# pc_max86150_breakout_qwiic2part_part2.net
KiCad netlist of a schematic drawn in EAGLE
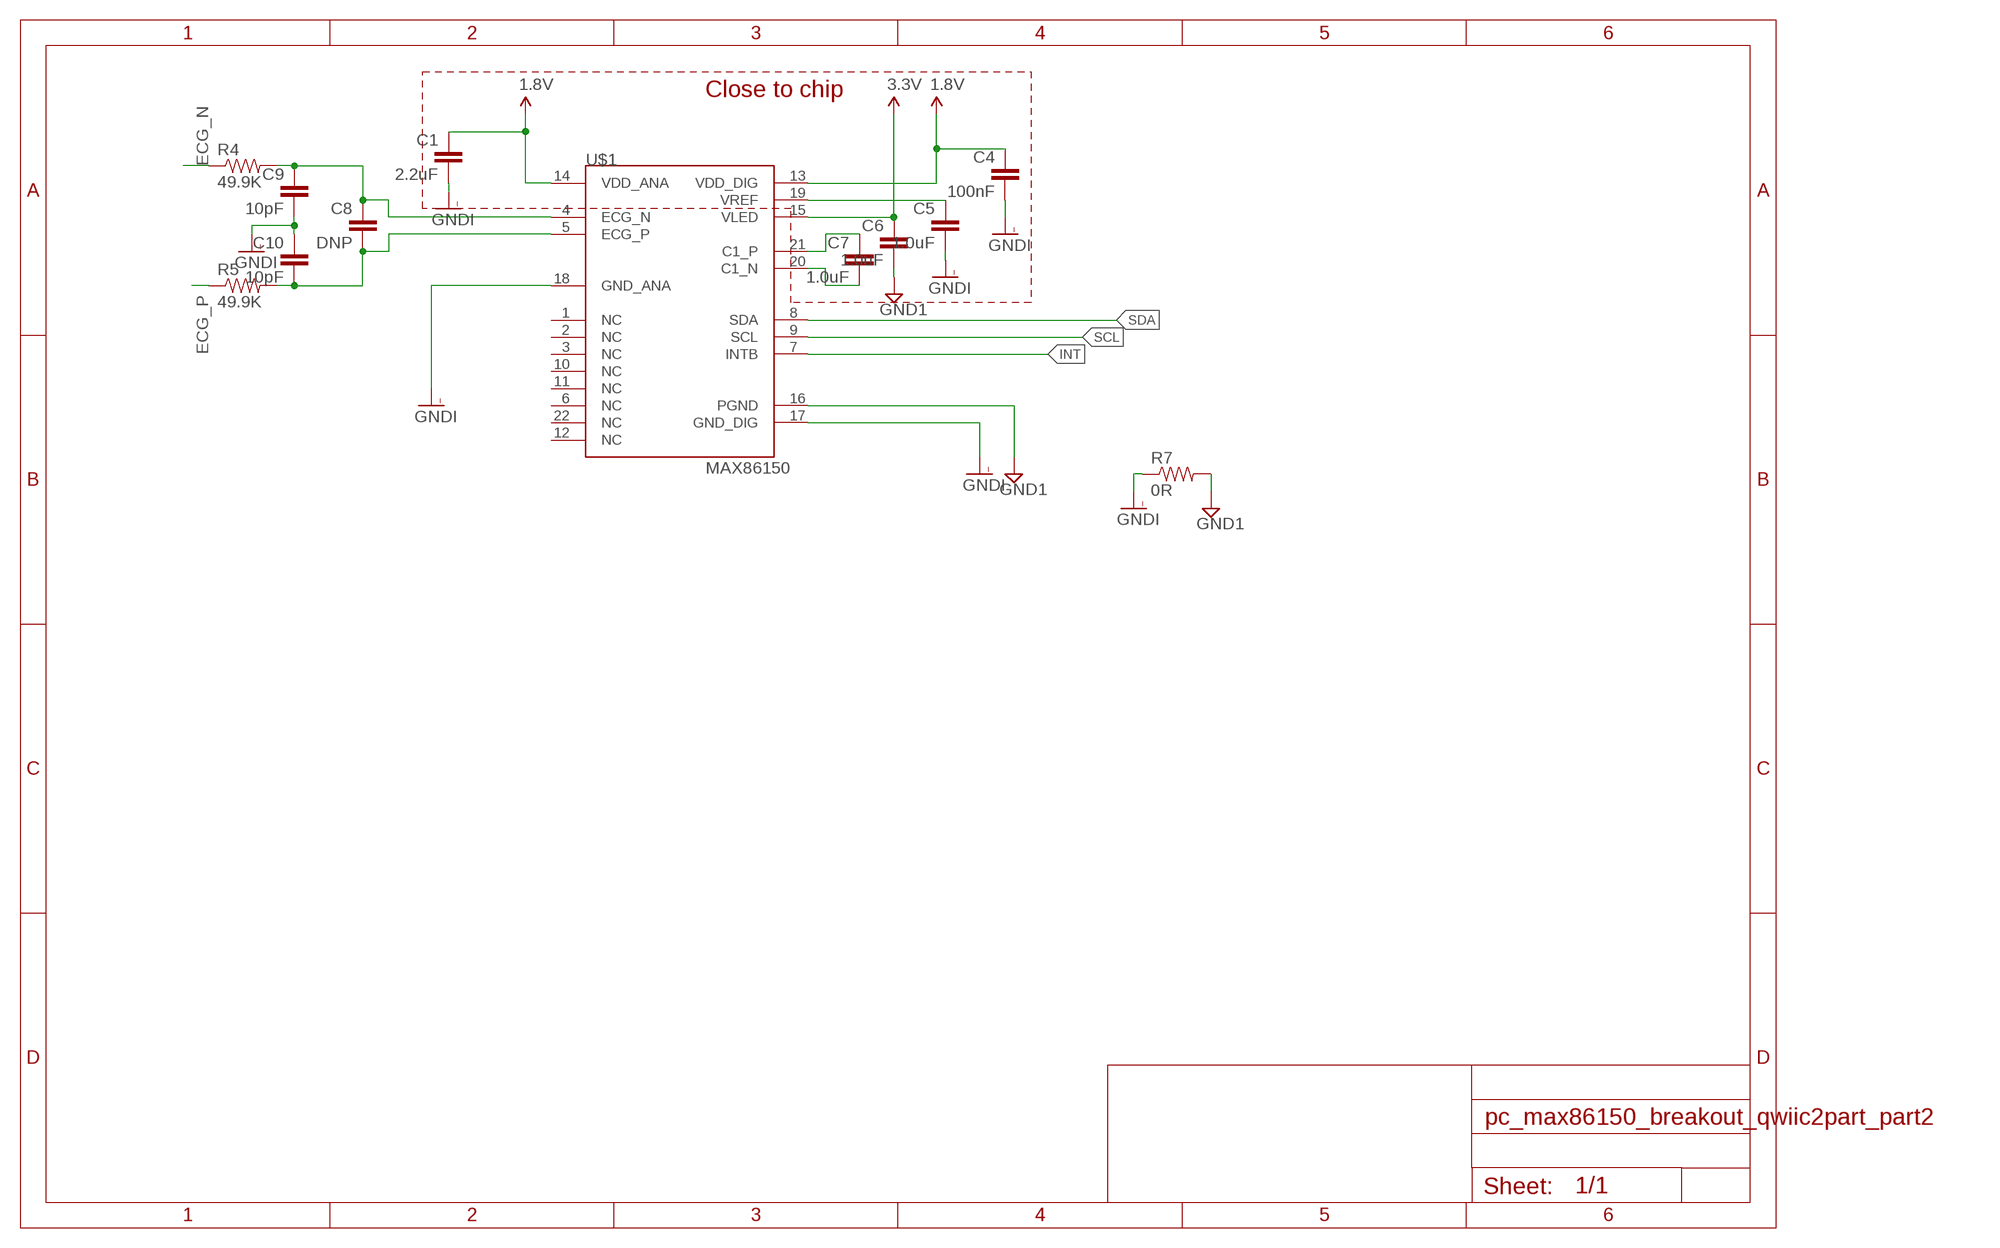
[diagram p0: schematic, sheet 1]

(export (version "E")
  (design (tool "Eeschema 10.0.6"))
  (components
    (comp (ref "C1")
      (value "2.2uF")
      (footprint "eagle-import:0402")
      (libsource (lib "eagle-import") (part "1.0UF-0402-16V-10%"))
    )
    (comp (ref "C4")
      (value "100nF")
      (footprint "eagle-import:0402")
      (libsource (lib "eagle-import") (part "1.0UF-0402-16V-10%"))
    )
    (comp (ref "C5")
      (value "1.0uF")
      (footprint "eagle-import:0402")
      (libsource (lib "eagle-import") (part "1.0UF-0402-16V-10%"))
    )
    (comp (ref "C6")
      (value "1.0uF")
      (footprint "eagle-import:0402")
      (libsource (lib "eagle-import") (part "1.0UF-0402-16V-10%"))
    )
    (comp (ref "C7")
      (value "1.0uF")
      (footprint "eagle-import:0402")
      (libsource (lib "eagle-import") (part "1.0UF-0402-16V-10%"))
    )
    (comp (ref "C8")
      (value "DNP")
      (footprint "eagle-import:0402")
      (libsource (lib "eagle-import") (part "1.0UF-0402-16V-10%"))
    )
    (comp (ref "C9")
      (value "10pF")
      (footprint "eagle-import:0402")
      (libsource (lib "eagle-import") (part "1.0UF-0402-16V-10%"))
    )
    (comp (ref "C10")
      (value "10pF")
      (footprint "eagle-import:0402")
      (libsource (lib "eagle-import") (part "1.0UF-0402-16V-10%"))
    )
    (comp (ref "R4")
      (value "49.9K")
      (footprint "eagle-import:0402-RES")
      (libsource (lib "eagle-import") (part "RESISTOR0402-RES"))
    )
    (comp (ref "R5")
      (value "49.9K")
      (footprint "eagle-import:0402-RES")
      (libsource (lib "eagle-import") (part "RESISTOR0402-RES"))
    )
    (comp (ref "R7")
      (value "0R")
      (footprint "eagle-import:0402-RES")
      (libsource (lib "eagle-import") (part "RESISTOR0402-RES"))
    )
    (comp (ref "U$1")
      (value "MAX86150")
      (footprint "eagle-import:MAX86150")
      (libsource (lib "eagle-import") (part "MAX86150"))
    )
  )
  (nets
    (net (code "1") (name "/ECG_N") (class "Default")
      (node (ref "R4") (pin "1") (pinfunction "1_1") (pintype "passive"))
    )
    (net (code "2") (name "/ECG_P") (class "Default")
      (node (ref "R5") (pin "1") (pinfunction "1_1") (pintype "passive"))
    )
    (net (code "3") (name "1.8V") (class "Default")
      (node (ref "C1") (pin "1") (pinfunction "1_1") (pintype "passive"))
      (node (ref "C4") (pin "1") (pinfunction "1_1") (pintype "passive"))
      (node (ref "U$1") (pin "13") (pinfunction "VDD_DIG_13") (pintype "bidirectional"))
      (node (ref "U$1") (pin "14") (pinfunction "VDD_ANA_14") (pintype "bidirectional"))
    )
    (net (code "4") (name "3.3V") (class "Default")
      (node (ref "C6") (pin "1") (pinfunction "1_1") (pintype "passive"))
      (node (ref "U$1") (pin "15") (pinfunction "VLED_15") (pintype "bidirectional"))
    )
    (net (code "5") (name "GND1") (class "Default")
      (node (ref "C6") (pin "2") (pinfunction "2_2") (pintype "passive"))
      (node (ref "R7") (pin "2") (pinfunction "2_2") (pintype "passive"))
      (node (ref "U$1") (pin "16") (pinfunction "PGND_16") (pintype "bidirectional"))
    )
    (net (code "6") (name "GNDI") (class "Default")
      (node (ref "C1") (pin "2") (pinfunction "2_2") (pintype "passive"))
      (node (ref "C10") (pin "1") (pinfunction "1_1") (pintype "passive"))
      (node (ref "C4") (pin "2") (pinfunction "2_2") (pintype "passive"))
      (node (ref "C5") (pin "2") (pinfunction "2_2") (pintype "passive"))
      (node (ref "C9") (pin "2") (pinfunction "2_2") (pintype "passive"))
      (node (ref "R7") (pin "1") (pinfunction "1_1") (pintype "passive"))
      (node (ref "U$1") (pin "17") (pinfunction "GND_DIG_17") (pintype "bidirectional"))
      (node (ref "U$1") (pin "18") (pinfunction "GND_ANA_18") (pintype "bidirectional"))
    )
    (net (code "7") (name "INT") (class "Default")
      (node (ref "U$1") (pin "7") (pinfunction "INTB_7") (pintype "bidirectional"))
    )
    (net (code "8") (name "Net-(U$1-C1_N)") (class "Default")
      (node (ref "C7") (pin "2") (pinfunction "2_2") (pintype "passive"))
      (node (ref "U$1") (pin "20") (pinfunction "C1_N_20") (pintype "bidirectional"))
    )
    (net (code "9") (name "Net-(U$1-C1_P)") (class "Default")
      (node (ref "C7") (pin "1") (pinfunction "1_1") (pintype "passive"))
      (node (ref "U$1") (pin "21") (pinfunction "C1_P_21") (pintype "bidirectional"))
    )
    (net (code "10") (name "Net-(U$1-ECG_N)") (class "Default")
      (node (ref "C8") (pin "1") (pinfunction "1_1") (pintype "passive"))
      (node (ref "C9") (pin "1") (pinfunction "1_1") (pintype "passive"))
      (node (ref "R4") (pin "2") (pinfunction "2_2") (pintype "passive"))
      (node (ref "U$1") (pin "4") (pinfunction "ECG_N_4") (pintype "bidirectional"))
    )
    (net (code "11") (name "Net-(U$1-ECG_P)") (class "Default")
      (node (ref "C10") (pin "2") (pinfunction "2_2") (pintype "passive"))
      (node (ref "C8") (pin "2") (pinfunction "2_2") (pintype "passive"))
      (node (ref "R5") (pin "2") (pinfunction "2_2") (pintype "passive"))
      (node (ref "U$1") (pin "5") (pinfunction "ECG_P_5") (pintype "bidirectional"))
    )
    (net (code "12") (name "Net-(U$1-VREF)") (class "Default")
      (node (ref "C5") (pin "1") (pinfunction "1_1") (pintype "passive"))
      (node (ref "U$1") (pin "19") (pinfunction "VREF_19") (pintype "bidirectional"))
    )
    (net (code "13") (name "SCL") (class "Default")
      (node (ref "U$1") (pin "9") (pinfunction "SCL_9") (pintype "bidirectional"))
    )
    (net (code "14") (name "SDA") (class "Default")
      (node (ref "U$1") (pin "8") (pinfunction "SDA_8") (pintype "bidirectional"))
    )
    (net (code "15") (name "unconnected-(U$1-NC-Pad1)") (class "Default")
      (node (ref "U$1") (pin "1") (pinfunction "NC_1") (pintype "bidirectional"))
    )
    (net (code "16") (name "unconnected-(U$1-NC-Pad2)") (class "Default")
      (node (ref "U$1") (pin "2") (pinfunction "NC_2") (pintype "bidirectional"))
    )
    (net (code "17") (name "unconnected-(U$1-NC-Pad3)") (class "Default")
      (node (ref "U$1") (pin "3") (pinfunction "NC_3") (pintype "bidirectional"))
    )
    (net (code "18") (name "unconnected-(U$1-NC-Pad6)") (class "Default")
      (node (ref "U$1") (pin "6") (pinfunction "NC_6") (pintype "bidirectional"))
    )
    (net (code "19") (name "unconnected-(U$1-NC-Pad10)") (class "Default")
      (node (ref "U$1") (pin "10") (pinfunction "NC_10") (pintype "bidirectional"))
    )
    (net (code "20") (name "unconnected-(U$1-NC-Pad11)") (class "Default")
      (node (ref "U$1") (pin "11") (pinfunction "NC_11") (pintype "bidirectional"))
    )
    (net (code "21") (name "unconnected-(U$1-NC-Pad12)") (class "Default")
      (node (ref "U$1") (pin "12") (pinfunction "NC_12") (pintype "bidirectional"))
    )
    (net (code "22") (name "unconnected-(U$1-NC-Pad22)") (class "Default")
      (node (ref "U$1") (pin "22") (pinfunction "NC_22") (pintype "bidirectional"))
    )
  )
)
